# 02-MCU.net
KiCad netlist of a schematic drawn in Altium Designer
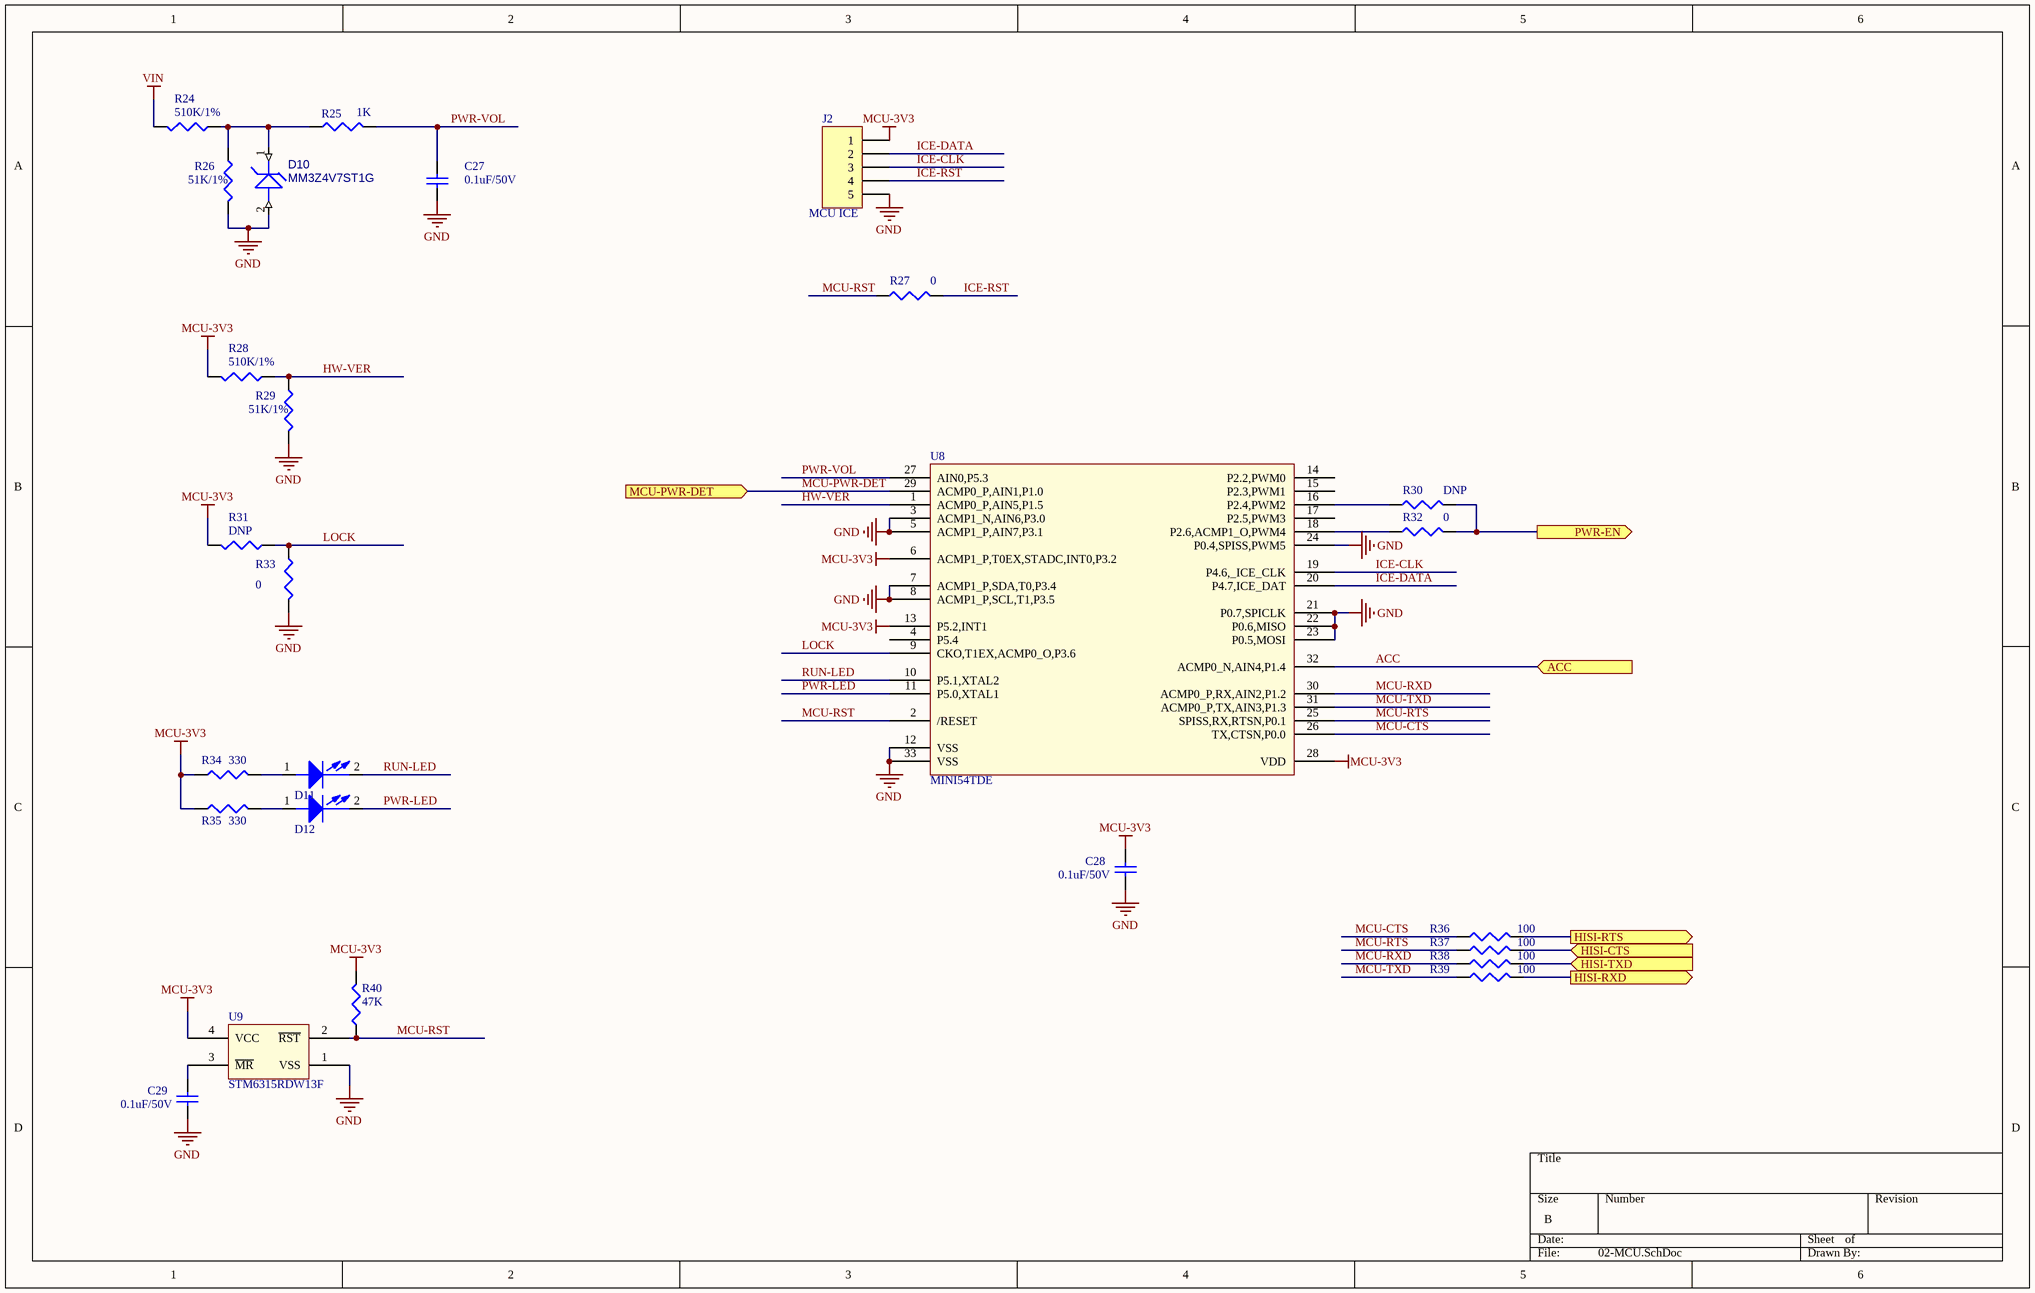
[diagram p0: 02-MCU.SchDoc]

(export (version "E")
  (design (tool "Eeschema 10.0.6"))
  (components
    (comp (ref "C27")
      (value "0.1uF/50V")
      (footprint "0402")
      (description "Capacitor")
      (fields (field (name "PUBLISHER") "Altium Limited"))
      (libsource (lib "Miscellaneous Devices") (part "Cap"))
    )
    (comp (ref "C28")
      (value "0.1uF/50V")
      (footprint "0402")
      (description "Capacitor")
      (fields (field (name "PUBLISHER") "Altium Limited"))
      (libsource (lib "Miscellaneous Devices") (part "Cap"))
    )
    (comp (ref "C29")
      (value "0.1uF/50V")
      (footprint "0402")
      (description "Capacitor")
      (fields (field (name "PUBLISHER") "Altium Limited"))
      (libsource (lib "Miscellaneous Devices") (part "Cap"))
    )
    (comp (ref "D10")
      (value "MM3Z4V7ST1G")
      (footprint "SOD323F")
      (libsource (lib "*") (part "MMGZ5231BPTLL34"))
    )
    (comp (ref "D11") (value "LED GREEN") (footprint "LED0603") (libsource (lib "*") (part "LN01401_1")))
    (comp (ref "D12") (value "LED GREEN") (footprint "LED0603") (libsource (lib "*") (part "LN01401_1")))
    (comp (ref "J2")
      (value "MCU ICE")
      (footprint "HDR1X5")
      (description "Header, 5-Pin")
      (fields (field (name "PUBLISHER") "Altium Limited"))
      (libsource (lib "Miscellaneous Connectors") (part "Header 5"))
    )
    (comp (ref "R24")
      (value "510K/1%")
      (footprint "0402")
      (description "Resistor")
      (fields (field (name "PUBLISHER") "Altium Limited"))
      (libsource (lib "Miscellaneous Devices") (part "Res3"))
    )
    (comp (ref "R25")
      (value "1K")
      (footprint "0402")
      (description "Resistor")
      (fields (field (name "PUBLISHER") "Altium Limited"))
      (libsource (lib "Miscellaneous Devices") (part "Res3"))
    )
    (comp (ref "R26")
      (value "51K/1%")
      (footprint "0402")
      (description "Resistor")
      (fields (field (name "PUBLISHER") "Altium Limited"))
      (libsource (lib "Miscellaneous Devices") (part "Res3"))
    )
    (comp (ref "R27")
      (value "0")
      (footprint "0402")
      (description "Resistor")
      (fields (field (name "PUBLISHER") "Altium Limited"))
      (libsource (lib "Miscellaneous Devices") (part "Res3"))
    )
    (comp (ref "R28")
      (value "510K/1%")
      (footprint "0402")
      (description "Resistor")
      (fields (field (name "PUBLISHER") "Altium Limited"))
      (libsource (lib "Miscellaneous Devices") (part "Res3"))
    )
    (comp (ref "R29")
      (value "51K/1%")
      (footprint "0402")
      (description "Resistor")
      (fields (field (name "PUBLISHER") "Altium Limited"))
      (libsource (lib "Miscellaneous Devices") (part "Res3"))
    )
    (comp (ref "R30")
      (value "DNP")
      (footprint "0402")
      (description "Resistor")
      (fields (field (name "PUBLISHER") "Altium Limited"))
      (libsource (lib "Miscellaneous Devices") (part "Res3"))
    )
    (comp (ref "R31")
      (value "DNP")
      (footprint "0402")
      (description "Resistor")
      (fields (field (name "PUBLISHER") "Altium Limited"))
      (libsource (lib "Miscellaneous Devices") (part "Res3"))
    )
    (comp (ref "R32")
      (value "0")
      (footprint "0402")
      (description "Resistor")
      (fields (field (name "PUBLISHER") "Altium Limited"))
      (libsource (lib "Miscellaneous Devices") (part "Res3"))
    )
    (comp (ref "R33")
      (value "0")
      (footprint "0402")
      (description "Resistor")
      (fields (field (name "PUBLISHER") "Altium Limited"))
      (libsource (lib "Miscellaneous Devices") (part "Res3"))
    )
    (comp (ref "R34") (value "330") (footprint "0402") (libsource (lib "*") (part "CR16-1003FM")))
    (comp (ref "R35") (value "330") (footprint "0402") (libsource (lib "*") (part "CR16-1003FM")))
    (comp (ref "R36")
      (value "100")
      (footprint "0402")
      (description "Resistor")
      (fields (field (name "PUBLISHER") "Altium Limited"))
      (libsource (lib "Miscellaneous Devices") (part "Res3"))
    )
    (comp (ref "R37")
      (value "100")
      (footprint "0402")
      (description "Resistor")
      (fields (field (name "PUBLISHER") "Altium Limited"))
      (libsource (lib "Miscellaneous Devices") (part "Res3"))
    )
    (comp (ref "R38")
      (value "100")
      (footprint "0402")
      (description "Resistor")
      (fields (field (name "PUBLISHER") "Altium Limited"))
      (libsource (lib "Miscellaneous Devices") (part "Res3"))
    )
    (comp (ref "R39")
      (value "100")
      (footprint "0402")
      (description "Resistor")
      (fields (field (name "PUBLISHER") "Altium Limited"))
      (libsource (lib "Miscellaneous Devices") (part "Res3"))
    )
    (comp (ref "R40")
      (value "47K")
      (footprint "0402")
      (description "Resistor")
      (fields (field (name "PUBLISHER") "Altium Limited"))
      (libsource (lib "Miscellaneous Devices") (part "Res3"))
    )
    (comp (ref "U8") (value "MINI54TDE") (footprint "QFN33") (libsource (lib "Schlib") (part "MINI54TDE")))
    (comp (ref "U9")
      (value "STM6315RDW13F")
      (footprint "SOT143-4")
      (libsource (lib "Schlib") (part "STM6315"))
    )
  )
  (nets
    (net (code "1") (name "/ACC") (class "Default")
      (node (ref "U8") (pin "32") (pinfunction "ACMP0_N,AIN4,P1.4_32") (pintype "passive"))
    )
    (net (code "2") (name "/HISI-CTS") (class "Default")
      (node (ref "R37") (pin "2") (pinfunction "2_2") (pintype "passive"))
    )
    (net (code "3") (name "/HISI-RTS") (class "Default")
      (node (ref "R36") (pin "2") (pinfunction "2_2") (pintype "passive"))
    )
    (net (code "4") (name "/HISI-RXD") (class "Default")
      (node (ref "R39") (pin "2") (pinfunction "2_2") (pintype "passive"))
    )
    (net (code "5") (name "/HISI-TXD") (class "Default")
      (node (ref "R38") (pin "2") (pinfunction "2_2") (pintype "passive"))
    )
    (net (code "6") (name "/HW-VER") (class "Default")
      (node (ref "R28") (pin "1") (pinfunction "1_1") (pintype "passive"))
      (node (ref "R29") (pin "1") (pinfunction "1_1") (pintype "passive"))
      (node (ref "U8") (pin "1") (pinfunction "ACMP0_P,AIN5,P1.5_1") (pintype "passive"))
    )
    (net (code "7") (name "/ICE-CLK") (class "Default")
      (node (ref "J2") (pin "3") (pinfunction "3_3") (pintype "passive"))
      (node (ref "U8") (pin "19") (pinfunction "P4.6,_ICE_CLK_19") (pintype "passive"))
    )
    (net (code "8") (name "/ICE-DATA") (class "Default")
      (node (ref "J2") (pin "2") (pinfunction "2_2") (pintype "passive"))
      (node (ref "U8") (pin "20") (pinfunction "P4.7,ICE_DAT_20") (pintype "passive"))
    )
    (net (code "9") (name "/ICE-RST") (class "Default")
      (node (ref "J2") (pin "4") (pinfunction "4_4") (pintype "passive"))
      (node (ref "R27") (pin "2") (pinfunction "2_2") (pintype "passive"))
    )
    (net (code "10") (name "/LOCK") (class "Default")
      (node (ref "R31") (pin "1") (pinfunction "1_1") (pintype "passive"))
      (node (ref "R33") (pin "1") (pinfunction "1_1") (pintype "passive"))
      (node (ref "U8") (pin "9") (pinfunction "CKO,T1EX,ACMP0_O,P3.6_9") (pintype "passive"))
    )
    (net (code "11") (name "/MCU-CTS") (class "Default")
      (node (ref "R36") (pin "1") (pinfunction "1_1") (pintype "passive"))
      (node (ref "U8") (pin "26") (pinfunction "TX,CTSN,P0.0_26") (pintype "passive"))
    )
    (net (code "12") (name "/MCU-PWR-DET") (class "Default")
      (node (ref "U8") (pin "29") (pinfunction "ACMP0_P,AIN1,P1.0_29") (pintype "passive"))
    )
    (net (code "13") (name "/MCU-RST") (class "Default")
      (node (ref "R27") (pin "1") (pinfunction "1_1") (pintype "passive"))
      (node (ref "R40") (pin "1") (pinfunction "1_1") (pintype "passive"))
      (node (ref "U8") (pin "2") (pinfunction "/RESET_2") (pintype "passive"))
      (node (ref "U9") (pin "2") (pinfunction "~{RST}_2") (pintype "passive"))
    )
    (net (code "14") (name "/MCU-RTS") (class "Default")
      (node (ref "R37") (pin "1") (pinfunction "1_1") (pintype "passive"))
      (node (ref "U8") (pin "25") (pinfunction "SPISS,RX,RTSN,P0.1_25") (pintype "passive"))
    )
    (net (code "15") (name "/MCU-RXD") (class "Default")
      (node (ref "R38") (pin "1") (pinfunction "1_1") (pintype "passive"))
      (node (ref "U8") (pin "30") (pinfunction "ACMP0_P,RX,AIN2,P1.2_30") (pintype "passive"))
    )
    (net (code "16") (name "/MCU-TXD") (class "Default")
      (node (ref "R39") (pin "1") (pinfunction "1_1") (pintype "passive"))
      (node (ref "U8") (pin "31") (pinfunction "ACMP0_P,TX,AIN3,P1.3_31") (pintype "passive"))
    )
    (net (code "17") (name "/PWR-EN") (class "Default")
      (node (ref "R30") (pin "2") (pinfunction "2_2") (pintype "passive"))
      (node (ref "R32") (pin "2") (pinfunction "2_2") (pintype "passive"))
    )
    (net (code "18") (name "/PWR-LED") (class "Default")
      (node (ref "D12") (pin "2") (pinfunction "CATHODE_2") (pintype "passive"))
      (node (ref "U8") (pin "11") (pinfunction "P5.0,XTAL1_11") (pintype "passive"))
    )
    (net (code "19") (name "/PWR-VOL") (class "Default")
      (node (ref "C27") (pin "1") (pinfunction "1_1") (pintype "passive"))
      (node (ref "R25") (pin "2") (pinfunction "2_2") (pintype "passive"))
      (node (ref "U8") (pin "27") (pinfunction "AIN0,P5.3_27") (pintype "passive"))
    )
    (net (code "20") (name "/RUN-LED") (class "Default")
      (node (ref "D11") (pin "2") (pinfunction "CATHODE_2") (pintype "passive"))
      (node (ref "U8") (pin "10") (pinfunction "P5.1,XTAL2_10") (pintype "passive"))
    )
    (net (code "21") (name "GND") (class "Default")
      (node (ref "C27") (pin "2") (pinfunction "2_2") (pintype "passive"))
      (node (ref "C28") (pin "2") (pinfunction "2_2") (pintype "passive"))
      (node (ref "C29") (pin "2") (pinfunction "2_2") (pintype "passive"))
      (node (ref "D10") (pin "2") (pinfunction "2_2") (pintype "input"))
      (node (ref "J2") (pin "5") (pinfunction "5_5") (pintype "passive"))
      (node (ref "R26") (pin "2") (pinfunction "2_2") (pintype "passive"))
      (node (ref "R29") (pin "2") (pinfunction "2_2") (pintype "passive"))
      (node (ref "R33") (pin "2") (pinfunction "2_2") (pintype "passive"))
      (node (ref "U8") (pin "12") (pinfunction "VSS_12") (pintype "passive"))
      (node (ref "U8") (pin "21") (pinfunction "P0.7,SPICLK_21") (pintype "passive"))
      (node (ref "U8") (pin "22") (pinfunction "P0.6,MISO_22") (pintype "passive"))
      (node (ref "U8") (pin "23") (pinfunction "P0.5,MOSI_23") (pintype "passive"))
      (node (ref "U8") (pin "24") (pinfunction "P0.4,SPISS,PWM5_24") (pintype "passive"))
      (node (ref "U8") (pin "3") (pinfunction "ACMP1_N,AIN6,P3.0_3") (pintype "passive"))
      (node (ref "U8") (pin "33") (pinfunction "VSS_33") (pintype "passive"))
      (node (ref "U8") (pin "5") (pinfunction "ACMP1_P,AIN7,P3.1_5") (pintype "passive"))
      (node (ref "U8") (pin "7") (pinfunction "ACMP1_P,SDA,T0,P3.4_7") (pintype "passive"))
      (node (ref "U8") (pin "8") (pinfunction "ACMP1_P,SCL,T1,P3.5_8") (pintype "passive"))
      (node (ref "U9") (pin "1") (pinfunction "VSS_1") (pintype "passive"))
    )
    (net (code "22") (name "MCU-3V3") (class "Default")
      (node (ref "C28") (pin "1") (pinfunction "1_1") (pintype "passive"))
      (node (ref "J2") (pin "1") (pinfunction "1_1") (pintype "passive"))
      (node (ref "R28") (pin "2") (pinfunction "2_2") (pintype "passive"))
      (node (ref "R31") (pin "2") (pinfunction "2_2") (pintype "passive"))
      (node (ref "R34") (pin "1") (pinfunction "1_1") (pintype "passive"))
      (node (ref "R35") (pin "1") (pinfunction "1_1") (pintype "passive"))
      (node (ref "R40") (pin "2") (pinfunction "2_2") (pintype "passive"))
      (node (ref "U8") (pin "13") (pinfunction "P5.2,INT1_13") (pintype "passive"))
      (node (ref "U8") (pin "28") (pinfunction "VDD_28") (pintype "passive"))
      (node (ref "U8") (pin "6") (pinfunction "ACMP1_P,T0EX,STADC,INT0,P3.2_6") (pintype "passive"))
      (node (ref "U9") (pin "4") (pinfunction "VCC_4") (pintype "passive"))
    )
    (net (code "23") (name "Net-(D10-Pad1)") (class "Default")
      (node (ref "D10") (pin "1") (pinfunction "1_1") (pintype "input"))
      (node (ref "R24") (pin "1") (pinfunction "1_1") (pintype "passive"))
      (node (ref "R25") (pin "1") (pinfunction "1_1") (pintype "passive"))
      (node (ref "R26") (pin "1") (pinfunction "1_1") (pintype "passive"))
    )
    (net (code "24") (name "Net-(D11-ANODE)") (class "Default")
      (node (ref "D11") (pin "1") (pinfunction "ANODE_1") (pintype "passive"))
      (node (ref "R34") (pin "2") (pinfunction "2_2") (pintype "passive"))
    )
    (net (code "25") (name "Net-(D12-ANODE)") (class "Default")
      (node (ref "D12") (pin "1") (pinfunction "ANODE_1") (pintype "passive"))
      (node (ref "R35") (pin "2") (pinfunction "2_2") (pintype "passive"))
    )
    (net (code "26") (name "Net-(U8-P2.4,PWM2)") (class "Default")
      (node (ref "R30") (pin "1") (pinfunction "1_1") (pintype "passive"))
      (node (ref "U8") (pin "16") (pinfunction "P2.4,PWM2_16") (pintype "passive"))
    )
    (net (code "27") (name "Net-(U8-P2.6,ACMP1_O,PWM4)") (class "Default")
      (node (ref "R32") (pin "1") (pinfunction "1_1") (pintype "passive"))
      (node (ref "U8") (pin "18") (pinfunction "P2.6,ACMP1_O,PWM4_18") (pintype "passive"))
    )
    (net (code "28") (name "Net-(U9-~{MR})") (class "Default")
      (node (ref "C29") (pin "1") (pinfunction "1_1") (pintype "passive"))
      (node (ref "U9") (pin "3") (pinfunction "~{MR}_3") (pintype "passive"))
    )
    (net (code "29") (name "VIN") (class "Default")
      (node (ref "R24") (pin "2") (pinfunction "2_2") (pintype "passive"))
    )
    (net (code "30") (name "unconnected-(U8-P2.2,PWM0-Pad14)") (class "Default")
      (node (ref "U8") (pin "14") (pinfunction "P2.2,PWM0_14") (pintype "passive"))
    )
    (net (code "31") (name "unconnected-(U8-P2.3,PWM1-Pad15)") (class "Default")
      (node (ref "U8") (pin "15") (pinfunction "P2.3,PWM1_15") (pintype "passive"))
    )
    (net (code "32") (name "unconnected-(U8-P2.5,PWM3-Pad17)") (class "Default")
      (node (ref "U8") (pin "17") (pinfunction "P2.5,PWM3_17") (pintype "passive"))
    )
    (net (code "33") (name "unconnected-(U8-P5.4-Pad4)") (class "Default")
      (node (ref "U8") (pin "4") (pinfunction "P5.4_4") (pintype "passive"))
    )
  )
)
